# cpOD.net
KiCad netlist of a schematic drawn in EAGLE
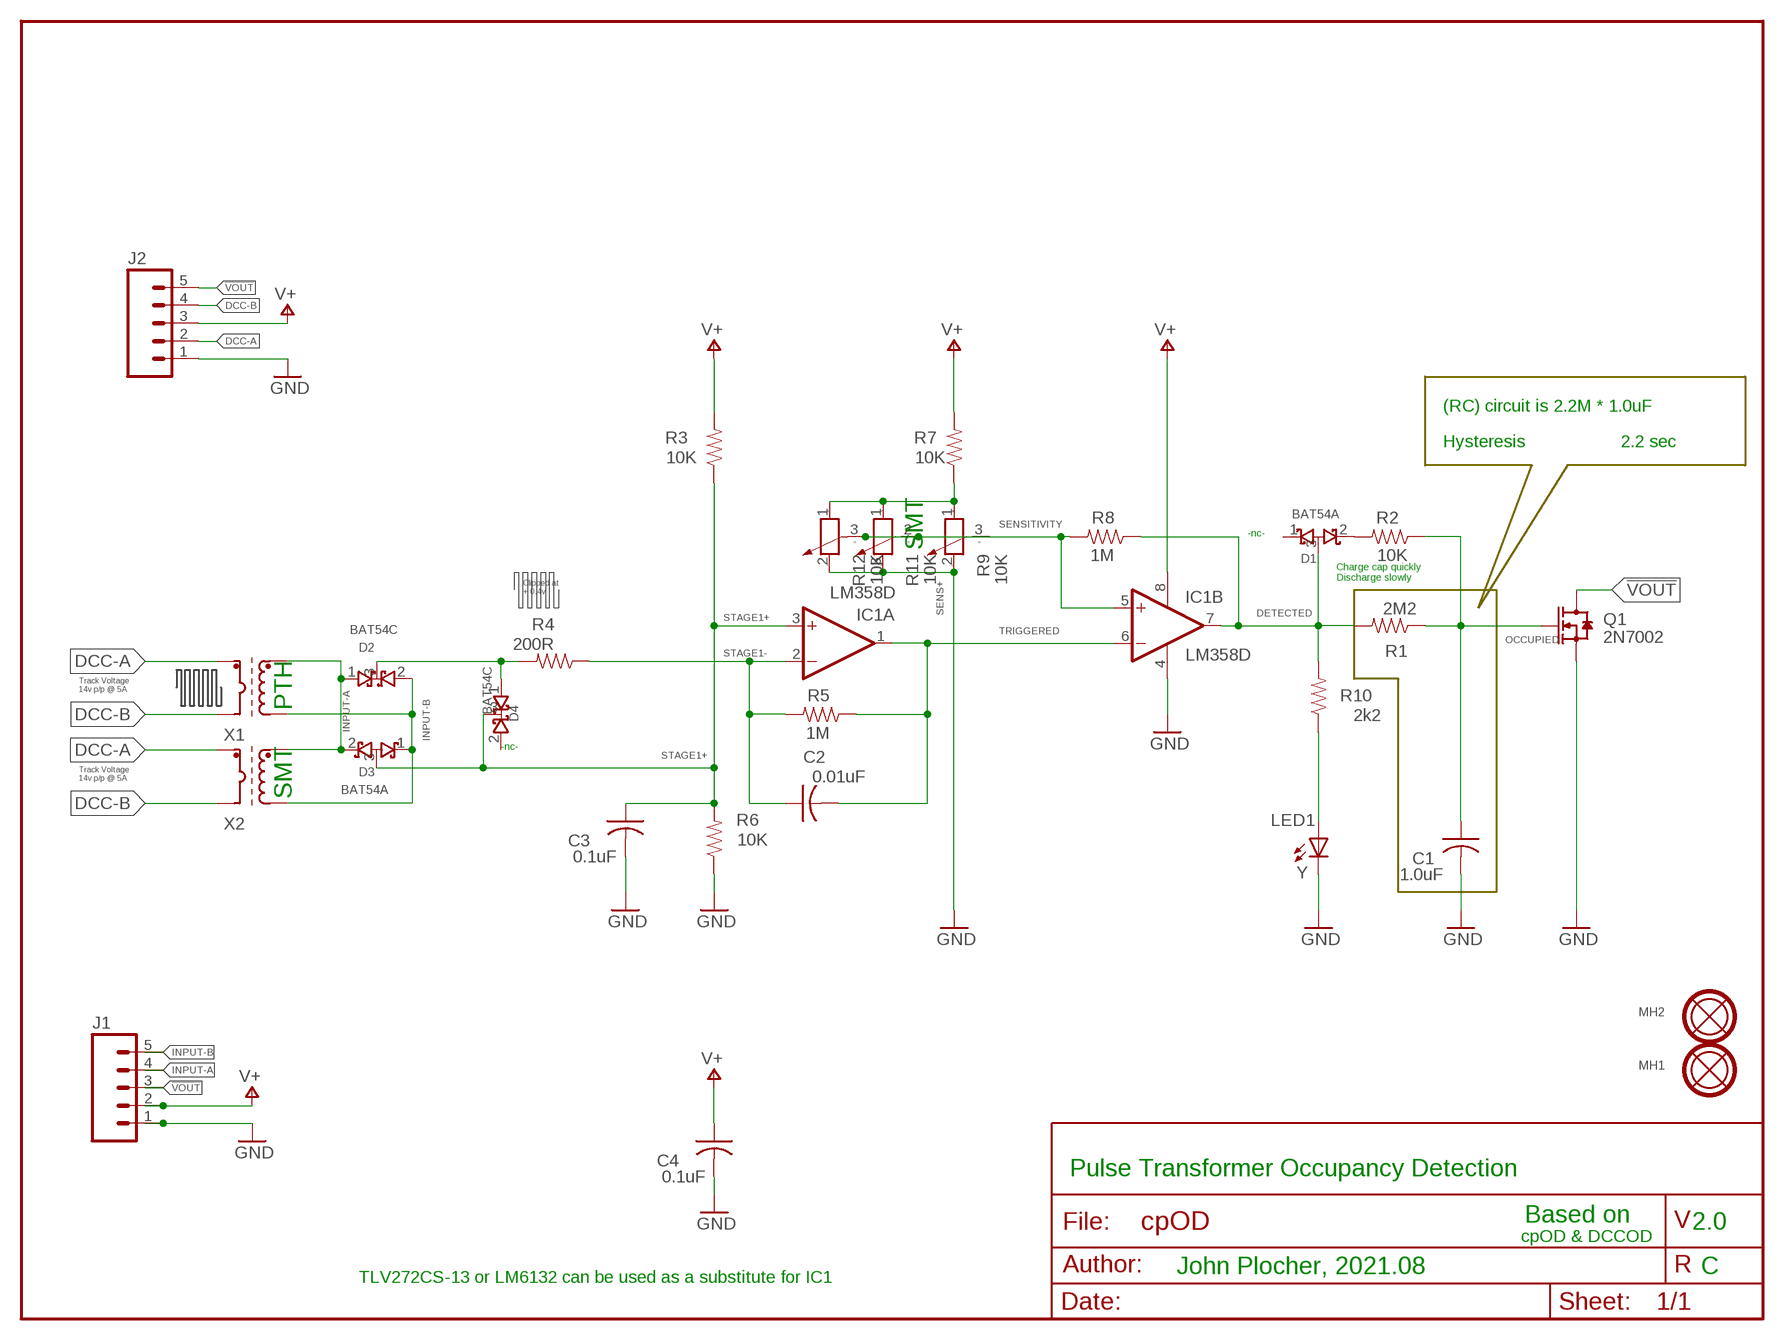
[diagram p0: schematic, sheet 1]

(export (version "E")
  (design (tool "Eeschema 10.0.6"))
  (components
    (comp (ref "C1")
      (value "1.0uF")
      (footprint "eagle-import:0603-CAP")
      (libsource (lib "eagle-import") (part "CAP0603"))
    )
    (comp (ref "C2")
      (value "0.01uF")
      (footprint "eagle-import:0603-CAP")
      (libsource (lib "eagle-import") (part "CAP0603"))
    )
    (comp (ref "C3")
      (value "0.1uF")
      (footprint "eagle-import:0603-CAP")
      (libsource (lib "eagle-import") (part "CAP0603"))
    )
    (comp (ref "C4")
      (value "0.1uF")
      (footprint "eagle-import:0603-CAP")
      (libsource (lib "eagle-import") (part "CAP0603"))
    )
    (comp (ref "D1")
      (value "BAT54A")
      (footprint "eagle-import:SOT23")
      (libsource (lib "eagle-import") (part "DIODE-BAT54A23"))
    )
    (comp (ref "D2")
      (value "BAT54C")
      (footprint "eagle-import:SOT23")
      (libsource (lib "eagle-import") (part "DIODE-BAT54C23"))
    )
    (comp (ref "D3")
      (value "BAT54A")
      (footprint "eagle-import:SOT23")
      (libsource (lib "eagle-import") (part "DIODE-BAT54A23"))
    )
    (comp (ref "D4")
      (value "BAT54C")
      (footprint "eagle-import:SOT23")
      (libsource (lib "eagle-import") (part "DIODE-BAT54C23"))
    )
    (comp (ref "IC1")
      (value "LM358D")
      (footprint "eagle-import:SO-8")
      (libsource (lib "eagle-import") (part "LM6132A"))
    )
    (comp (ref "J1")
      (value "CONNECTOR-M05PTH")
      (footprint "eagle-import:1X05")
      (libsource (lib "eagle-import") (part "CONNECTOR-M05PTH"))
    )
    (comp (ref "J2")
      (value "CONNECTOR-M051.56")
      (footprint "eagle-import:KK-156-5")
      (libsource (lib "eagle-import") (part "CONNECTOR-M051.56"))
    )
    (comp (ref "LED1")
      (value "Y")
      (footprint "eagle-import:0603-LED")
      (libsource (lib "eagle-import") (part "LED0603-LED"))
    )
    (comp (ref "MH1")
      (value "MOUNTINGHOLEL")
      (footprint "eagle-import:MOUNTINGHOLE-L")
      (libsource (lib "eagle-import") (part "MOUNTINGHOLEL"))
    )
    (comp (ref "MH2")
      (value "MOUNTINGHOLEL")
      (footprint "eagle-import:MOUNTINGHOLE-L")
      (libsource (lib "eagle-import") (part "MOUNTINGHOLEL"))
    )
    (comp (ref "Q1")
      (value "2N7002")
      (footprint "eagle-import:SOT23")
      (libsource (lib "eagle-import") (part "MOSFET-N--?SOT232N7002"))
    )
    (comp (ref "R1")
      (value "2M2")
      (footprint "eagle-import:0603-RES")
      (libsource (lib "eagle-import") (part "R0603-RES"))
    )
    (comp (ref "R2")
      (value "10K")
      (footprint "eagle-import:0603-RES")
      (libsource (lib "eagle-import") (part "R0603-RES"))
    )
    (comp (ref "R3")
      (value "10K")
      (footprint "eagle-import:0603-RES")
      (libsource (lib "eagle-import") (part "R0603-RES"))
    )
    (comp (ref "R4")
      (value "200R")
      (footprint "eagle-import:0603-RES")
      (libsource (lib "eagle-import") (part "R0603-RES"))
    )
    (comp (ref "R5")
      (value "1M")
      (footprint "eagle-import:0603-RES")
      (libsource (lib "eagle-import") (part "R0603-RES"))
    )
    (comp (ref "R6")
      (value "10K")
      (footprint "eagle-import:0603-RES")
      (libsource (lib "eagle-import") (part "R0603-RES"))
    )
    (comp (ref "R7")
      (value "10K")
      (footprint "eagle-import:0603-RES")
      (libsource (lib "eagle-import") (part "R0603-RES"))
    )
    (comp (ref "R8")
      (value "1M")
      (footprint "eagle-import:0603-RES")
      (libsource (lib "eagle-import") (part "R0603-RES"))
    )
    (comp (ref "R9")
      (value "10K")
      (footprint "eagle-import:ST-4")
      (libsource (lib "eagle-import") (part "R-POTENTIOMETERETB"))
    )
    (comp (ref "R10")
      (value "2k2")
      (footprint "eagle-import:0603-RES")
      (libsource (lib "eagle-import") (part "R0603-RES"))
    )
    (comp (ref "R11")
      (value "10K")
      (footprint "eagle-import:PT-10S")
      (libsource (lib "eagle-import") (part "R-POTENTIOMETERPT-10S"))
    )
    (comp (ref "R12")
      (value "10K")
      (footprint "eagle-import:TC33X")
      (libsource (lib "eagle-import") (part "R-POTENTIOMETERTC33X"))
    )
    (comp (ref "X1")
      (value "PULSE-TRANSFORMERPTH-RB")
      (footprint "eagle-import:TH-T4B")
      (libsource (lib "eagle-import") (part "PULSE-TRANSFORMERPTH-RB"))
    )
    (comp (ref "X2")
      (value "PULSE-TRANSFORMERM")
      (footprint "eagle-import:M5300")
      (libsource (lib "eagle-import") (part "PULSE-TRANSFORMERM"))
    )
  )
  (nets
    (net (code "1") (name "/DETECTED") (class "Default")
      (node (ref "D1") (pin "3") (pinfunction "COM_3") (pintype "bidirectional"))
      (node (ref "IC1") (pin "7") (pinfunction "OUT_7") (pintype "output"))
      (node (ref "R1") (pin "2") (pinfunction "2_2") (pintype "passive"))
      (node (ref "R10") (pin "2") (pinfunction "2_2") (pintype "passive"))
      (node (ref "R8") (pin "1") (pinfunction "1_1") (pintype "passive"))
    )
    (net (code "2") (name "/OCCUPIED") (class "Default")
      (node (ref "C1") (pin "1") (pinfunction "1_1") (pintype "passive"))
      (node (ref "Q1") (pin "1") (pinfunction "G_1") (pintype "passive"))
      (node (ref "R1") (pin "1") (pinfunction "1_1") (pintype "passive"))
      (node (ref "R2") (pin "1") (pinfunction "1_1") (pintype "passive"))
    )
    (net (code "3") (name "/SENS+") (class "Default")
      (node (ref "R11") (pin "1") (pinfunction "A_1") (pintype "passive"))
      (node (ref "R12") (pin "1") (pinfunction "A_1") (pintype "passive"))
      (node (ref "R7") (pin "1") (pinfunction "1_1") (pintype "passive"))
      (node (ref "R9") (pin "1") (pinfunction "A_1") (pintype "passive"))
    )
    (net (code "4") (name "/SENSITIVITY") (class "Default")
      (node (ref "IC1") (pin "5") (pinfunction "+IN_5") (pintype "input"))
      (node (ref "R11") (pin "2") (pinfunction "S_2") (pintype "passive"))
      (node (ref "R12") (pin "3") (pinfunction "S_3") (pintype "passive"))
      (node (ref "R8") (pin "2") (pinfunction "2_2") (pintype "passive"))
      (node (ref "R9") (pin "3") (pinfunction "S_3") (pintype "passive"))
    )
    (net (code "5") (name "/STAGE1+") (class "Default")
      (node (ref "C3") (pin "1") (pinfunction "1_1") (pintype "passive"))
      (node (ref "D3") (pin "3") (pinfunction "COM_3") (pintype "bidirectional"))
      (node (ref "D4") (pin "3") (pinfunction "COM_3") (pintype "bidirectional"))
      (node (ref "IC1") (pin "3") (pinfunction "+IN_3") (pintype "input"))
      (node (ref "R3") (pin "1") (pinfunction "1_1") (pintype "passive"))
      (node (ref "R6") (pin "2") (pinfunction "2_2") (pintype "passive"))
    )
    (net (code "6") (name "/STAGE1-") (class "Default")
      (node (ref "C2") (pin "1") (pinfunction "1_1") (pintype "passive"))
      (node (ref "IC1") (pin "2") (pinfunction "-IN_2") (pintype "input"))
      (node (ref "R4") (pin "1") (pinfunction "1_1") (pintype "passive"))
      (node (ref "R5") (pin "2") (pinfunction "2_2") (pintype "passive"))
    )
    (net (code "7") (name "/TRIGGERED") (class "Default")
      (node (ref "C2") (pin "2") (pinfunction "2_2") (pintype "passive"))
      (node (ref "IC1") (pin "1") (pinfunction "OUT_1") (pintype "output"))
      (node (ref "IC1") (pin "6") (pinfunction "-IN_6") (pintype "input"))
      (node (ref "R5") (pin "1") (pinfunction "1_1") (pintype "passive"))
    )
    (net (code "8") (name "/~{VOUT}") (class "Default")
      (node (ref "J1") (pin "3") (pinfunction "3_3") (pintype "passive"))
      (node (ref "J2") (pin "5") (pinfunction "5_5") (pintype "passive"))
      (node (ref "Q1") (pin "3") (pinfunction "D_3") (pintype "passive"))
    )
    (net (code "9") (name "DCC-A") (class "Default")
      (node (ref "J2") (pin "2") (pinfunction "2_2") (pintype "passive"))
      (node (ref "X1") (pin "P2") (pinfunction "DCC-B_P2") (pintype "passive"))
      (node (ref "X2") (pin "8") (pinfunction "DCC-B_8") (pintype "passive"))
    )
    (net (code "10") (name "DCC-B") (class "Default")
      (node (ref "J2") (pin "4") (pinfunction "4_4") (pintype "passive"))
      (node (ref "X1") (pin "P1") (pinfunction "DCC-A_P1") (pintype "passive"))
      (node (ref "X2") (pin "7") (pinfunction "DCC-A_7") (pintype "passive"))
    )
    (net (code "11") (name "GND") (class "Default")
      (node (ref "C1") (pin "2") (pinfunction "2_2") (pintype "passive"))
      (node (ref "C3") (pin "2") (pinfunction "2_2") (pintype "passive"))
      (node (ref "C4") (pin "2") (pinfunction "2_2") (pintype "passive"))
      (node (ref "IC1") (pin "4") (pinfunction "V-_4") (pintype "power_in"))
      (node (ref "J1") (pin "1") (pinfunction "1_1") (pintype "passive"))
      (node (ref "J2") (pin "1") (pinfunction "1_1") (pintype "passive"))
      (node (ref "LED1") (pin "C") (pinfunction "C_C") (pintype "passive"))
      (node (ref "Q1") (pin "2") (pinfunction "S_2") (pintype "passive"))
      (node (ref "R11") (pin "3") (pinfunction "E_3") (pintype "passive"))
      (node (ref "R12") (pin "2") (pinfunction "E_2") (pintype "passive"))
      (node (ref "R6") (pin "1") (pinfunction "1_1") (pintype "passive"))
      (node (ref "R9") (pin "2") (pinfunction "E_2") (pintype "passive"))
    )
    (net (code "12") (name "INPUT-A") (class "Default")
      (node (ref "D2") (pin "1") (pinfunction "A1_1") (pintype "bidirectional"))
      (node (ref "D3") (pin "2") (pinfunction "C2_2") (pintype "bidirectional"))
      (node (ref "J1") (pin "4") (pinfunction "4_4") (pintype "passive"))
      (node (ref "X1") (pin "S2") (pinfunction "OUT-B_S2") (pintype "passive"))
      (node (ref "X2") (pin "1") (pinfunction "OUT-B_1") (pintype "passive"))
    )
    (net (code "13") (name "INPUT-B") (class "Default")
      (node (ref "D2") (pin "2") (pinfunction "A2_2") (pintype "bidirectional"))
      (node (ref "D3") (pin "1") (pinfunction "C1_1") (pintype "bidirectional"))
      (node (ref "J1") (pin "5") (pinfunction "5_5") (pintype "passive"))
      (node (ref "X1") (pin "S1") (pinfunction "OUT-A_S1") (pintype "passive"))
      (node (ref "X2") (pin "3") (pinfunction "OUT-A_3") (pintype "passive"))
    )
    (net (code "14") (name "Net-(D1-C2)") (class "Default")
      (node (ref "D1") (pin "2") (pinfunction "C2_2") (pintype "bidirectional"))
      (node (ref "R2") (pin "2") (pinfunction "2_2") (pintype "passive"))
    )
    (net (code "15") (name "Net-(D2-COM)") (class "Default")
      (node (ref "D2") (pin "3") (pinfunction "COM_3") (pintype "bidirectional"))
      (node (ref "D4") (pin "1") (pinfunction "A1_1") (pintype "bidirectional"))
      (node (ref "R4") (pin "2") (pinfunction "2_2") (pintype "passive"))
    )
    (net (code "16") (name "Net-(LED1-PadA)") (class "Default")
      (node (ref "LED1") (pin "A") (pinfunction "A_A") (pintype "passive"))
      (node (ref "R10") (pin "1") (pinfunction "1_1") (pintype "passive"))
    )
    (net (code "17") (name "V+") (class "Default")
      (node (ref "C4") (pin "1") (pinfunction "1_1") (pintype "passive"))
      (node (ref "IC1") (pin "8") (pinfunction "V+_8") (pintype "power_in"))
      (node (ref "J1") (pin "2") (pinfunction "2_2") (pintype "passive"))
      (node (ref "J2") (pin "3") (pinfunction "3_3") (pintype "passive"))
      (node (ref "R3") (pin "2") (pinfunction "2_2") (pintype "passive"))
      (node (ref "R7") (pin "2") (pinfunction "2_2") (pintype "passive"))
    )
    (net (code "18") (name "unconnected-(D1-C1-Pad1)") (class "Default")
      (node (ref "D1") (pin "1") (pinfunction "C1_1") (pintype "bidirectional"))
    )
    (net (code "19") (name "unconnected-(D4-A2-Pad2)") (class "Default")
      (node (ref "D4") (pin "2") (pinfunction "A2_2") (pintype "bidirectional"))
    )
  )
)
